# o_clone_rev_f.net
KiCad netlist of a schematic drawn in EAGLE
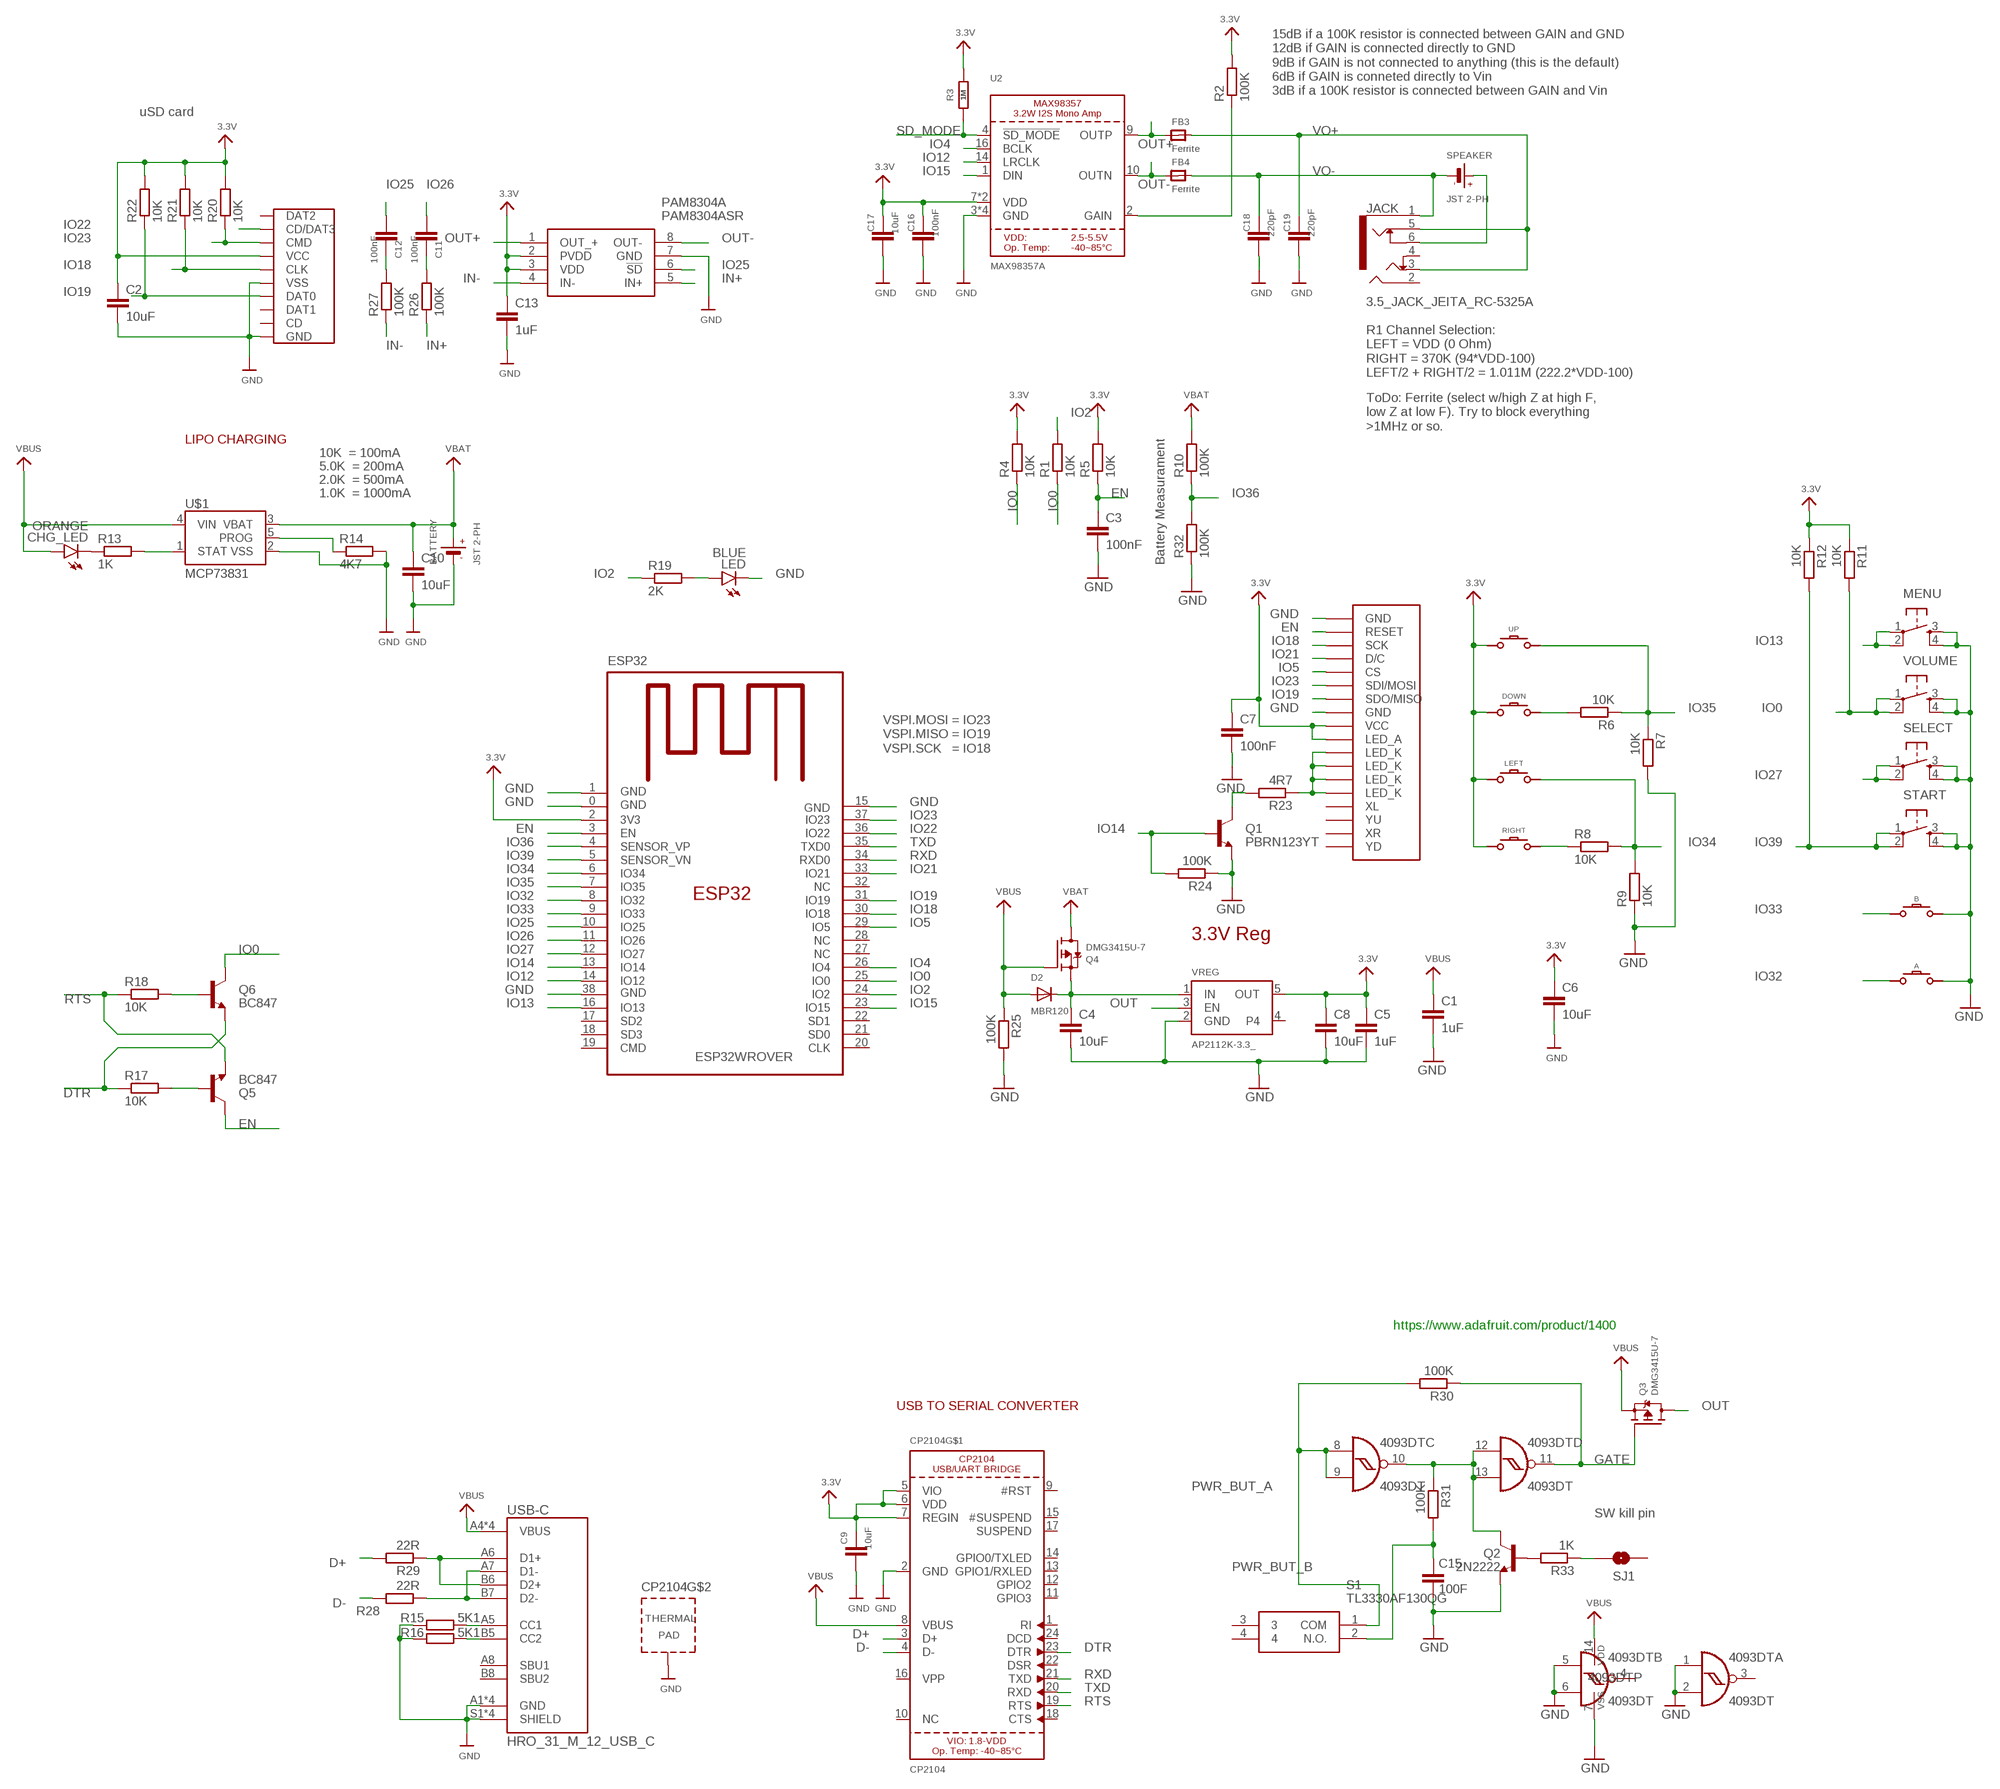
[diagram p0: schematic, sheet 1]

(export (version "E")
  (design (tool "Eeschema 10.0.6"))
  (components
    (comp (ref "4093DT")
      (value "4093DT")
      (footprint "eagle-import:MC14093B-TSSOP14")
      (libsource (lib "eagle-import") (part "4093DT"))
    )
    (comp (ref "A")
      (value "CONDUCTIVE_BUTTONCONDUCTIVE_BUTTON_THICK")
      (footprint "eagle-import:CONDUCTIVE_BUTTON_THICK")
      (libsource (lib "eagle-import") (part "CONDUCTIVE_BUTTONCONDUCTIVE_BUTTON_THICK"))
    )
    (comp (ref "B")
      (value "CONDUCTIVE_BUTTONCONDUCTIVE_BUTTON_THICK")
      (footprint "eagle-import:CONDUCTIVE_BUTTON_THICK")
      (libsource (lib "eagle-import") (part "CONDUCTIVE_BUTTONCONDUCTIVE_BUTTON_THICK"))
    )
    (comp (ref "BATTERY")
      (value "JST 2-PH")
      (footprint "eagle-import:JSTPH2")
      (libsource (lib "eagle-import") (part "JST_CONNECTOR"))
    )
    (comp (ref "C1")
      (value "1uF")
      (footprint "eagle-import:C0805")
      (libsource (lib "eagle-import") (part "C-EUC0805"))
    )
    (comp (ref "C2")
      (value "10uF")
      (footprint "eagle-import:C0805")
      (libsource (lib "eagle-import") (part "C-EUC0805"))
    )
    (comp (ref "C3")
      (value "100nF")
      (footprint "eagle-import:C0805")
      (libsource (lib "eagle-import") (part "C-EUC0805"))
    )
    (comp (ref "C4")
      (value "10uF")
      (footprint "eagle-import:C0805")
      (libsource (lib "eagle-import") (part "C-EUC0805"))
    )
    (comp (ref "C5")
      (value "1uF")
      (footprint "eagle-import:C0805")
      (libsource (lib "eagle-import") (part "C-EUC0805"))
    )
    (comp (ref "C6")
      (value "10uF")
      (footprint "eagle-import:C0805")
      (libsource (lib "eagle-import") (part "C-EUC0805"))
    )
    (comp (ref "C7")
      (value "100nF")
      (footprint "eagle-import:C0805")
      (libsource (lib "eagle-import") (part "C-EUC0805"))
    )
    (comp (ref "C8")
      (value "10uF")
      (footprint "eagle-import:C0805")
      (libsource (lib "eagle-import") (part "C-EUC0805"))
    )
    (comp (ref "C9")
      (value "10uF")
      (footprint "eagle-import:C0805")
      (libsource (lib "eagle-import") (part "C-EUC0805"))
    )
    (comp (ref "C10")
      (value "10uF")
      (footprint "eagle-import:C0805")
      (libsource (lib "eagle-import") (part "C-EUC0805"))
    )
    (comp (ref "C11")
      (value "100nF")
      (footprint "eagle-import:C0805")
      (libsource (lib "eagle-import") (part "C-EUC0805"))
    )
    (comp (ref "C12")
      (value "100nF")
      (footprint "eagle-import:C0805")
      (libsource (lib "eagle-import") (part "C-EUC0805"))
    )
    (comp (ref "C13")
      (value "1uF")
      (footprint "eagle-import:C0805")
      (libsource (lib "eagle-import") (part "C-EUC0805"))
    )
    (comp (ref "C15")
      (value "100F")
      (footprint "eagle-import:C0805")
      (libsource (lib "eagle-import") (part "C-EUC0805"))
    )
    (comp (ref "C16")
      (value "100nF")
      (footprint "eagle-import:C0805")
      (libsource (lib "eagle-import") (part "C-EUC0805"))
    )
    (comp (ref "C17")
      (value "10uF")
      (footprint "eagle-import:C0805")
      (libsource (lib "eagle-import") (part "C-EUC0805"))
    )
    (comp (ref "C18")
      (value "220pF")
      (footprint "eagle-import:C0805")
      (libsource (lib "eagle-import") (part "C-EUC0805"))
    )
    (comp (ref "C19")
      (value "220pF")
      (footprint "eagle-import:C0805")
      (libsource (lib "eagle-import") (part "C-EUC0805"))
    )
    (comp (ref "CHG_LED")
      (value "ORANGE")
      (footprint "eagle-import:CHIPLED_0805")
      (libsource (lib "eagle-import") (part "LEDCHIPLED_0805"))
    )
    (comp (ref "CP2104")
      (value "CP2104")
      (footprint "eagle-import:QFN24_4MM_SMSC")
      (libsource (lib "eagle-import") (part "CP2104"))
    )
    (comp (ref "D2")
      (value "MBR120")
      (footprint "eagle-import:SOD-123")
      (libsource (lib "eagle-import") (part "DIODESOD-123"))
    )
    (comp (ref "DOWN")
      (value "CONDUCTIVE_BUTTONCONDUCTIVE_BUTTON_DIRECTIONAL_THICK")
      (footprint "eagle-import:CONDUCTIVE_BUTTON_DIRECTIONAL_THICK")
      (libsource (lib "eagle-import") (part "CONDUCTIVE_BUTTONCONDUCTIVE_BUTTON_DIRECTIONAL_THICK"))
    )
    (comp (ref "ESP32")
      (value "ESP32WROVER")
      (footprint "eagle-import:ESP32WROVER")
      (libsource (lib "eagle-import") (part "ESP32WROVER"))
    )
    (comp (ref "FB3")
      (value "Ferrite")
      (footprint "eagle-import:0805")
      (libsource (lib "eagle-import") (part "FERRITE0805"))
    )
    (comp (ref "FB4")
      (value "Ferrite")
      (footprint "eagle-import:0805")
      (libsource (lib "eagle-import") (part "FERRITE0805"))
    )
    (comp (ref "JACK")
      (value "3.5_JACK_JEITA_RC-5325A")
      (footprint "eagle-import:3.5_JACK_JEITA_RC-5325A")
      (libsource (lib "eagle-import") (part "3.5_JACK_JEITA_RC-5325A"))
    )
    (comp (ref "LCD")
      (value "ILI9341_3.2LCD_")
      (footprint "eagle-import:LI9341_3.2LCD")
      (libsource (lib "eagle-import") (part "ILI9341_3.2LCD_"))
    )
    (comp (ref "LED")
      (value "BLUE")
      (footprint "eagle-import:CHIPLED_0805")
      (libsource (lib "eagle-import") (part "LEDCHIPLED_0805"))
    )
    (comp (ref "LEFT")
      (value "CONDUCTIVE_BUTTONCONDUCTIVE_BUTTON_DIRECTIONAL_THICK")
      (footprint "eagle-import:CONDUCTIVE_BUTTON_DIRECTIONAL_THICK")
      (libsource (lib "eagle-import") (part "CONDUCTIVE_BUTTONCONDUCTIVE_BUTTON_DIRECTIONAL_THICK"))
    )
    (comp (ref "MENU")
      (value "TACTILE_SWITCHE_5X5_MICRO\"")
      (footprint "eagle-import:TACTILE_SWITCH_5X5_MICRO")
      (libsource (lib "eagle-import") (part "TACTILE_SWITCHE_5X5_MICRO{dblquote}"))
    )
    (comp (ref "PAM8304A")
      (value "PAM8304ASR")
      (footprint "eagle-import:SOP65P490X110-8N")
      (fields (field (name "MOUSER_PART_NUMBER") "621-PAM8304ASR"))
      (libsource (lib "eagle-import") (part "PAM8304ASR"))
    )
    (comp (ref "Q1")
      (value "PBRN123YT")
      (footprint "eagle-import:SOT23-3")
      (libsource (lib "eagle-import") (part "TRANSISTOR_NPNSOT23-3"))
    )
    (comp (ref "Q2")
      (value "2N2222")
      (footprint "eagle-import:SOT23-BEC")
      (libsource (lib "eagle-import") (part "-NPN-SOT23-BECMMBT2222ALT1"))
    )
    (comp (ref "Q3")
      (value "DMG3415U-7")
      (footprint "eagle-import:SOT23-WIDE@1")
      (libsource (lib "eagle-import") (part "MOSFET-PWIDE"))
    )
    (comp (ref "Q4")
      (value "DMG3415U-7")
      (footprint "eagle-import:SOT23-R")
      (libsource (lib "eagle-import") (part "MOSFET-P"))
    )
    (comp (ref "Q5")
      (value "BC847")
      (footprint "eagle-import:SOT23-3")
      (libsource (lib "eagle-import") (part "TRANSISTOR_NPNSOT23-3"))
    )
    (comp (ref "Q6")
      (value "BC847")
      (footprint "eagle-import:SOT23-3")
      (libsource (lib "eagle-import") (part "TRANSISTOR_NPNSOT23-3"))
    )
    (comp (ref "R1")
      (value "10K")
      (footprint "eagle-import:R0805")
      (libsource (lib "eagle-import") (part "R-EU_R0805"))
    )
    (comp (ref "R2")
      (value "100K")
      (footprint "eagle-import:R0805")
      (libsource (lib "eagle-import") (part "R-EU_R0805"))
    )
    (comp (ref "R3")
      (value "1M")
      (footprint "eagle-import:R0805")
      (libsource (lib "eagle-import") (part "R-EU_R0805"))
    )
    (comp (ref "R4")
      (value "10K")
      (footprint "eagle-import:R0805")
      (libsource (lib "eagle-import") (part "R-EU_R0805"))
    )
    (comp (ref "R5")
      (value "10K")
      (footprint "eagle-import:R0805")
      (libsource (lib "eagle-import") (part "R-EU_R0805"))
    )
    (comp (ref "R6")
      (value "10K")
      (footprint "eagle-import:R0805")
      (libsource (lib "eagle-import") (part "R-EU_R0805"))
    )
    (comp (ref "R7")
      (value "10K")
      (footprint "eagle-import:R0805")
      (libsource (lib "eagle-import") (part "R-EU_R0805"))
    )
    (comp (ref "R8")
      (value "10K")
      (footprint "eagle-import:R0805")
      (libsource (lib "eagle-import") (part "R-EU_R0805"))
    )
    (comp (ref "R9")
      (value "10K")
      (footprint "eagle-import:R0805")
      (libsource (lib "eagle-import") (part "R-EU_R0805"))
    )
    (comp (ref "R10")
      (value "100K")
      (footprint "eagle-import:R0805")
      (libsource (lib "eagle-import") (part "R-EU_R0805"))
    )
    (comp (ref "R11")
      (value "10K")
      (footprint "eagle-import:R0805")
      (libsource (lib "eagle-import") (part "R-EU_R0805"))
    )
    (comp (ref "R12")
      (value "10K")
      (footprint "eagle-import:R0805")
      (libsource (lib "eagle-import") (part "R-EU_R0805"))
    )
    (comp (ref "R13")
      (value "1K")
      (footprint "eagle-import:R0805")
      (libsource (lib "eagle-import") (part "R-EU_R0805"))
    )
    (comp (ref "R14")
      (value "4K7")
      (footprint "eagle-import:R0805")
      (libsource (lib "eagle-import") (part "R-EU_R0805"))
    )
    (comp (ref "R15")
      (value "5K1")
      (footprint "eagle-import:R0805")
      (libsource (lib "eagle-import") (part "R-EU_R0805"))
    )
    (comp (ref "R16")
      (value "5K1")
      (footprint "eagle-import:R0805")
      (libsource (lib "eagle-import") (part "R-EU_R0805"))
    )
    (comp (ref "R17")
      (value "10K")
      (footprint "eagle-import:R0805")
      (libsource (lib "eagle-import") (part "R-EU_R0805"))
    )
    (comp (ref "R18")
      (value "10K")
      (footprint "eagle-import:R0805")
      (libsource (lib "eagle-import") (part "R-EU_R0805"))
    )
    (comp (ref "R19")
      (value "2K")
      (footprint "eagle-import:R0805")
      (libsource (lib "eagle-import") (part "R-EU_R0805"))
    )
    (comp (ref "R20")
      (value "10K")
      (footprint "eagle-import:R0805")
      (libsource (lib "eagle-import") (part "R-EU_R0805"))
    )
    (comp (ref "R21")
      (value "10K")
      (footprint "eagle-import:R0805")
      (libsource (lib "eagle-import") (part "R-EU_R0805"))
    )
    (comp (ref "R22")
      (value "10K")
      (footprint "eagle-import:R0805")
      (libsource (lib "eagle-import") (part "R-EU_R0805"))
    )
    (comp (ref "R23")
      (value "4R7")
      (footprint "eagle-import:R0805")
      (libsource (lib "eagle-import") (part "R-EU_R0805"))
    )
    (comp (ref "R24")
      (value "100K")
      (footprint "eagle-import:R0805")
      (libsource (lib "eagle-import") (part "R-EU_R0805"))
    )
    (comp (ref "R25")
      (value "100K")
      (footprint "eagle-import:R0805")
      (libsource (lib "eagle-import") (part "R-EU_R0805"))
    )
    (comp (ref "R26")
      (value "100K")
      (footprint "eagle-import:R0805")
      (libsource (lib "eagle-import") (part "R-EU_R0805"))
    )
    (comp (ref "R27")
      (value "100K")
      (footprint "eagle-import:R0805")
      (libsource (lib "eagle-import") (part "R-EU_R0805"))
    )
    (comp (ref "R28")
      (value "22R")
      (footprint "eagle-import:R0805")
      (libsource (lib "eagle-import") (part "R-EU_R0805"))
    )
    (comp (ref "R29")
      (value "22R")
      (footprint "eagle-import:R0805")
      (libsource (lib "eagle-import") (part "R-EU_R0805"))
    )
    (comp (ref "R30")
      (value "100K")
      (footprint "eagle-import:R0805")
      (libsource (lib "eagle-import") (part "R-EU_R0805"))
    )
    (comp (ref "R31")
      (value "100K")
      (footprint "eagle-import:R0805")
      (libsource (lib "eagle-import") (part "R-EU_R0805"))
    )
    (comp (ref "R32")
      (value "100K")
      (footprint "eagle-import:R0805")
      (libsource (lib "eagle-import") (part "R-EU_R0805"))
    )
    (comp (ref "R33")
      (value "1K")
      (footprint "eagle-import:R0805")
      (libsource (lib "eagle-import") (part "R-EU_R0805"))
    )
    (comp (ref "RIGHT")
      (value "CONDUCTIVE_BUTTONCONDUCTIVE_BUTTON_DIRECTIONAL_THICK")
      (footprint "eagle-import:CONDUCTIVE_BUTTON_DIRECTIONAL_THICK")
      (libsource (lib "eagle-import") (part "CONDUCTIVE_BUTTONCONDUCTIVE_BUTTON_DIRECTIONAL_THICK"))
    )
    (comp (ref "S1")
      (value "TL3330AF130QG")
      (footprint "eagle-import:TL3330AF130QG")
      (fields (field (name "MOUSER_PART_NUMBER") "612-TL3330AF130QG"))
      (libsource (lib "eagle-import") (part "TL3330AF130QG"))
    )
    (comp (ref "SD_CARD")
      (value "MICRO_SD_CARD\"")
      (footprint "eagle-import:TFP09-2--12B")
      (libsource (lib "eagle-import") (part "MICRO_SD_CARD{dblquote}"))
    )
    (comp (ref "SELECT")
      (value "TACTILE_SWITCHE_5X5_MICRO\"")
      (footprint "eagle-import:TACTILE_SWITCH_5X5_MICRO")
      (libsource (lib "eagle-import") (part "TACTILE_SWITCHE_5X5_MICRO{dblquote}"))
    )
    (comp (ref "SJ1")
      (value "SOLDERJUMPERNO")
      (footprint "eagle-import:SJ_2S-NO")
      (libsource (lib "eagle-import") (part "SOLDERJUMPERNO"))
    )
    (comp (ref "SPEAKER")
      (value "JST 2-PH")
      (footprint "eagle-import:JSTPH2")
      (libsource (lib "eagle-import") (part "JST_CONNECTOR"))
    )
    (comp (ref "START")
      (value "TACTILE_SWITCHE_5X5_MICRO\"")
      (footprint "eagle-import:TACTILE_SWITCH_5X5_MICRO")
      (libsource (lib "eagle-import") (part "TACTILE_SWITCHE_5X5_MICRO{dblquote}"))
    )
    (comp (ref "U$1")
      (value "MCP73831")
      (footprint "eagle-import:SOT95P290X120-5")
      (libsource (lib "eagle-import") (part "MCP73831"))
    )
    (comp (ref "U2")
      (value "MAX98357A")
      (footprint "eagle-import:QFN16_3MM")
      (libsource (lib "eagle-import") (part "AUDIOAMP_MAX98357"))
    )
    (comp (ref "UP")
      (value "CONDUCTIVE_BUTTONCONDUCTIVE_BUTTON_DIRECTIONAL_THICK")
      (footprint "eagle-import:CONDUCTIVE_BUTTON_DIRECTIONAL_THICK")
      (libsource (lib "eagle-import") (part "CONDUCTIVE_BUTTONCONDUCTIVE_BUTTON_DIRECTIONAL_THICK"))
    )
    (comp (ref "USB-C")
      (value "HRO_31_M_12_USB_C")
      (footprint "eagle-import:HRO_31_M_12_USB_C")
      (libsource (lib "eagle-import") (part "HRO_31_M_12_USB_C"))
    )
    (comp (ref "VOLUME")
      (value "TACTILE_SWITCHE_5X5_MICRO\"")
      (footprint "eagle-import:TACTILE_SWITCH_5X5_MICRO")
      (libsource (lib "eagle-import") (part "TACTILE_SWITCHE_5X5_MICRO{dblquote}"))
    )
    (comp (ref "VREG")
      (value "AP2112K-3.3_")
      (footprint "eagle-import:SOT95P290X120-5")
      (libsource (lib "eagle-import") (part "AP2112K-3.3_"))
    )
  )
  (nets
    (net (code "1") (name "/D+") (class "Default")
      (node (ref "CP2104") (pin "3") (pinfunction "D+_3") (pintype "bidirectional"))
      (node (ref "R29") (pin "2") (pinfunction "2_2") (pintype "passive"))
    )
    (net (code "2") (name "/D-") (class "Default")
      (node (ref "CP2104") (pin "4") (pinfunction "D-_4") (pintype "bidirectional"))
      (node (ref "R28") (pin "2") (pinfunction "2_2") (pintype "passive"))
    )
    (net (code "3") (name "/DTR") (class "Default")
      (node (ref "CP2104") (pin "23") (pinfunction "DTR_23") (pintype "output"))
      (node (ref "Q6") (pin "2") (pinfunction "E_2") (pintype "passive"))
      (node (ref "R17") (pin "1") (pinfunction "1_1") (pintype "passive"))
    )
    (net (code "4") (name "/EN") (class "Default")
      (node (ref "C3") (pin "1") (pinfunction "1_1") (pintype "passive"))
      (node (ref "ESP32") (pin "3") (pinfunction "EN_3") (pintype "bidirectional"))
      (node (ref "LCD") (pin "P$2") (pinfunction "RESET_P$2") (pintype "bidirectional"))
      (node (ref "Q5") (pin "3") (pinfunction "C_3") (pintype "passive"))
      (node (ref "R5") (pin "1") (pinfunction "1_1") (pintype "passive"))
    )
    (net (code "5") (name "/GATE") (class "Default")
      (node (ref "4093DT") (pin "11") (pinfunction "O_11") (pintype "output"))
      (node (ref "Q3") (pin "1") (pinfunction "G_1") (pintype "passive"))
      (node (ref "R30") (pin "1") (pinfunction "1_1") (pintype "passive"))
    )
    (net (code "6") (name "/IN+") (class "Default")
      (node (ref "PAM8304A") (pin "5") (pinfunction "IN+_5") (pintype "bidirectional"))
      (node (ref "R26") (pin "1") (pinfunction "1_1") (pintype "passive"))
    )
    (net (code "7") (name "/IN-") (class "Default")
      (node (ref "PAM8304A") (pin "4") (pinfunction "IN-_4") (pintype "bidirectional"))
      (node (ref "R27") (pin "1") (pinfunction "1_1") (pintype "passive"))
    )
    (net (code "8") (name "/IO0") (class "Default")
      (node (ref "ESP32") (pin "25") (pinfunction "IO0_25") (pintype "bidirectional"))
      (node (ref "Q6") (pin "3") (pinfunction "C_3") (pintype "passive"))
      (node (ref "R1") (pin "1") (pinfunction "1_1") (pintype "passive"))
      (node (ref "R11") (pin "2") (pinfunction "2_2") (pintype "passive"))
      (node (ref "R4") (pin "1") (pinfunction "1_1") (pintype "passive"))
      (node (ref "VOLUME") (pin "1") (pinfunction "1_1") (pintype "passive"))
      (node (ref "VOLUME") (pin "2") (pinfunction "2_2") (pintype "passive"))
    )
    (net (code "9") (name "/IO2") (class "Default")
      (node (ref "ESP32") (pin "24") (pinfunction "IO2_24") (pintype "bidirectional"))
      (node (ref "R1") (pin "2") (pinfunction "2_2") (pintype "passive"))
      (node (ref "R19") (pin "1") (pinfunction "1_1") (pintype "passive"))
    )
    (net (code "10") (name "/IO4") (class "Default")
      (node (ref "ESP32") (pin "26") (pinfunction "IO4_26") (pintype "bidirectional"))
      (node (ref "U2") (pin "16") (pinfunction "BCLK_16") (pintype "bidirectional"))
    )
    (net (code "11") (name "/IO5") (class "Default")
      (node (ref "ESP32") (pin "29") (pinfunction "IO5_29") (pintype "bidirectional"))
      (node (ref "LCD") (pin "P$5") (pinfunction "CS_P$5") (pintype "bidirectional"))
    )
    (net (code "12") (name "/IO12") (class "Default")
      (node (ref "ESP32") (pin "14") (pinfunction "IO12_14") (pintype "bidirectional"))
      (node (ref "U2") (pin "14") (pinfunction "LRCLK_14") (pintype "bidirectional"))
    )
    (net (code "13") (name "/IO13") (class "Default")
      (node (ref "ESP32") (pin "16") (pinfunction "IO13_16") (pintype "bidirectional"))
      (node (ref "MENU") (pin "1") (pinfunction "1_1") (pintype "passive"))
      (node (ref "MENU") (pin "2") (pinfunction "2_2") (pintype "passive"))
    )
    (net (code "14") (name "/IO14") (class "Default")
      (node (ref "ESP32") (pin "13") (pinfunction "IO14_13") (pintype "bidirectional"))
      (node (ref "Q1") (pin "1") (pinfunction "B_1") (pintype "passive"))
      (node (ref "R24") (pin "2") (pinfunction "2_2") (pintype "passive"))
    )
    (net (code "15") (name "/IO15") (class "Default")
      (node (ref "ESP32") (pin "23") (pinfunction "IO15_23") (pintype "bidirectional"))
      (node (ref "U2") (pin "1") (pinfunction "DIN_1") (pintype "bidirectional"))
    )
    (net (code "16") (name "/IO18") (class "Default")
      (node (ref "ESP32") (pin "30") (pinfunction "IO18_30") (pintype "bidirectional"))
      (node (ref "LCD") (pin "P$3") (pinfunction "SCK_P$3") (pintype "bidirectional"))
      (node (ref "R21") (pin "1") (pinfunction "1_1") (pintype "passive"))
      (node (ref "SD_CARD") (pin "CLK") (pinfunction "CLK_CLK") (pintype "bidirectional"))
    )
    (net (code "17") (name "/IO19") (class "Default")
      (node (ref "ESP32") (pin "31") (pinfunction "IO19_31") (pintype "bidirectional"))
      (node (ref "LCD") (pin "P$7") (pinfunction "SDO/MISO_P$7") (pintype "bidirectional"))
      (node (ref "R22") (pin "1") (pinfunction "1_1") (pintype "passive"))
      (node (ref "SD_CARD") (pin "DAT0") (pinfunction "DAT0_DAT0") (pintype "bidirectional"))
    )
    (net (code "18") (name "/IO21") (class "Default")
      (node (ref "ESP32") (pin "33") (pinfunction "IO21_33") (pintype "bidirectional"))
      (node (ref "LCD") (pin "P$4") (pinfunction "D/C_P$4") (pintype "bidirectional"))
    )
    (net (code "19") (name "/IO22") (class "Default")
      (node (ref "ESP32") (pin "36") (pinfunction "IO22_36") (pintype "bidirectional"))
      (node (ref "SD_CARD") (pin "CD/DAT3") (pinfunction "CD/DAT3_CD/DAT3") (pintype "bidirectional"))
    )
    (net (code "20") (name "/IO23") (class "Default")
      (node (ref "ESP32") (pin "37") (pinfunction "IO23_37") (pintype "bidirectional"))
      (node (ref "LCD") (pin "P$6") (pinfunction "SDI/MOSI_P$6") (pintype "bidirectional"))
      (node (ref "R20") (pin "1") (pinfunction "1_1") (pintype "passive"))
      (node (ref "SD_CARD") (pin "CMD") (pinfunction "CMD_CMD") (pintype "bidirectional"))
    )
    (net (code "21") (name "/IO25") (class "Default")
      (node (ref "C12") (pin "2") (pinfunction "2_2") (pintype "passive"))
      (node (ref "ESP32") (pin "10") (pinfunction "IO25_10") (pintype "bidirectional"))
      (node (ref "PAM8304A") (pin "6") (pinfunction "~{SD}_6") (pintype "bidirectional"))
    )
    (net (code "22") (name "/IO26") (class "Default")
      (node (ref "C11") (pin "2") (pinfunction "2_2") (pintype "passive"))
      (node (ref "ESP32") (pin "11") (pinfunction "IO26_11") (pintype "bidirectional"))
    )
    (net (code "23") (name "/IO27") (class "Default")
      (node (ref "ESP32") (pin "12") (pinfunction "IO27_12") (pintype "bidirectional"))
      (node (ref "SELECT") (pin "1") (pinfunction "1_1") (pintype "passive"))
      (node (ref "SELECT") (pin "2") (pinfunction "2_2") (pintype "passive"))
    )
    (net (code "24") (name "/IO32") (class "Default")
      (node (ref "A") (pin "P$GND") (pinfunction "P$GND_P$GND") (pintype "bidirectional"))
      (node (ref "ESP32") (pin "8") (pinfunction "IO32_8") (pintype "bidirectional"))
    )
    (net (code "25") (name "/IO33") (class "Default")
      (node (ref "B") (pin "P$GND") (pinfunction "P$GND_P$GND") (pintype "bidirectional"))
      (node (ref "ESP32") (pin "9") (pinfunction "IO33_9") (pintype "bidirectional"))
    )
    (net (code "26") (name "/IO34") (class "Default")
      (node (ref "ESP32") (pin "6") (pinfunction "IO34_6") (pintype "bidirectional"))
      (node (ref "LEFT") (pin "P$ACTIVE") (pinfunction "P$ACTIVE_P$ACTIVE") (pintype "bidirectional"))
      (node (ref "R8") (pin "2") (pinfunction "2_2") (pintype "passive"))
      (node (ref "R9") (pin "2") (pinfunction "2_2") (pintype "passive"))
    )
    (net (code "27") (name "/IO35") (class "Default")
      (node (ref "ESP32") (pin "7") (pinfunction "IO35_7") (pintype "bidirectional"))
      (node (ref "R6") (pin "1") (pinfunction "1_1") (pintype "passive"))
      (node (ref "R7") (pin "1") (pinfunction "1_1") (pintype "passive"))
      (node (ref "UP") (pin "P$ACTIVE") (pinfunction "P$ACTIVE_P$ACTIVE") (pintype "bidirectional"))
    )
    (net (code "28") (name "/IO36") (class "Default")
      (node (ref "ESP32") (pin "4") (pinfunction "SENSOR_VP_4") (pintype "bidirectional"))
      (node (ref "R10") (pin "1") (pinfunction "1_1") (pintype "passive"))
      (node (ref "R32") (pin "2") (pinfunction "2_2") (pintype "passive"))
    )
    (net (code "29") (name "/IO39") (class "Default")
      (node (ref "ESP32") (pin "5") (pinfunction "SENSOR_VN_5") (pintype "bidirectional"))
      (node (ref "R12") (pin "2") (pinfunction "2_2") (pintype "passive"))
      (node (ref "START") (pin "1") (pinfunction "1_1") (pintype "passive"))
      (node (ref "START") (pin "2") (pinfunction "2_2") (pintype "passive"))
    )
    (net (code "30") (name "/OUT") (class "Default")
      (node (ref "Q3") (pin "3") (pinfunction "D_3") (pintype "passive"))
      (node (ref "VREG") (pin "3") (pinfunction "EN_3") (pintype "bidirectional"))
    )
    (net (code "31") (name "/OUT+") (class "Default")
      (node (ref "FB3") (pin "1") (pinfunction "P$1_1") (pintype "passive"))
      (node (ref "PAM8304A") (pin "1") (pinfunction "OUT_+_1") (pintype "bidirectional"))
      (node (ref "U2") (pin "9") (pinfunction "OUTP_9") (pintype "output"))
    )
    (net (code "32") (name "/OUT-") (class "Default")
      (node (ref "FB4") (pin "1") (pinfunction "P$1_1") (pintype "passive"))
      (node (ref "PAM8304A") (pin "8") (pinfunction "OUT-_8") (pintype "bidirectional"))
      (node (ref "U2") (pin "10") (pinfunction "OUTN_10") (pintype "output"))
    )
    (net (code "33") (name "/PWR_BUT_A") (class "Default")
      (node (ref "4093DT") (pin "8") (pinfunction "I0_8") (pintype "input"))
      (node (ref "4093DT") (pin "9") (pinfunction "I1_9") (pintype "input"))
      (node (ref "R30") (pin "2") (pinfunction "2_2") (pintype "passive"))
      (node (ref "S1") (pin "1") (pinfunction "COM_1") (pintype "bidirectional"))
    )
    (net (code "34") (name "/PWR_BUT_B") (class "Default")
      (node (ref "C15") (pin "1") (pinfunction "1_1") (pintype "passive"))
      (node (ref "R31") (pin "2") (pinfunction "2_2") (pintype "passive"))
      (node (ref "S1") (pin "2") (pinfunction "N.O._2") (pintype "bidirectional"))
    )
    (net (code "35") (name "/RTS") (class "Default")
      (node (ref "CP2104") (pin "19") (pinfunction "RTS_19") (pintype "output"))
      (node (ref "Q5") (pin "2") (pinfunction "E_2") (pintype "passive"))
      (node (ref "R18") (pin "1") (pinfunction "1_1") (pintype "passive"))
    )
    (net (code "36") (name "/RXD") (class "Default")
      (node (ref "CP2104") (pin "21") (pinfunction "TXD_21") (pintype "output"))
      (node (ref "ESP32") (pin "34") (pinfunction "RXD0_34") (pintype "bidirectional"))
    )
    (net (code "37") (name "/SD_MODE") (class "Default")
      (node (ref "R3") (pin "1") (pinfunction "1_1") (pintype "passive"))
      (node (ref "U2") (pin "4") (pinfunction "~{SD_MODE}_4") (pintype "bidirectional"))
    )
    (net (code "38") (name "/TXD") (class "Default")
      (node (ref "CP2104") (pin "20") (pinfunction "RXD_20") (pintype "input"))
      (node (ref "ESP32") (pin "35") (pinfunction "TXD0_35") (pintype "bidirectional"))
    )
    (net (code "39") (name "/VO+") (class "Default")
      (node (ref "C19") (pin "1") (pinfunction "1_1") (pintype "passive"))
      (node (ref "FB3") (pin "2") (pinfunction "P$2_2") (pintype "passive"))
      (node (ref "JACK") (pin "3") (pinfunction "3_3") (pintype "bidirectional"))
      (node (ref "JACK") (pin "5") (pinfunction "5_5") (pintype "bidirectional"))
    )
    (net (code "40") (name "/VO-") (class "Default")
      (node (ref "C18") (pin "1") (pinfunction "1_1") (pintype "passive"))
      (node (ref "FB4") (pin "2") (pinfunction "P$2_2") (pintype "passive"))
      (node (ref "JACK") (pin "1") (pinfunction "1_1") (pintype "bidirectional"))
      (node (ref "SPEAKER") (pin "1") (pinfunction "-_1") (pintype "passive"))
    )
    (net (code "41") (name "3.3V") (class "Default")
      (node (ref "C13") (pin "1") (pinfunction "1_1") (pintype "passive"))
      (node (ref "C16") (pin "1") (pinfunction "1_1") (pintype "passive"))
      (node (ref "C17") (pin "1") (pinfunction "1_1") (pintype "passive"))
      (node (ref "C2") (pin "1") (pinfunction "1_1") (pintype "passive"))
      (node (ref "C5") (pin "1") (pinfunction "1_1") (pintype "passive"))
      (node (ref "C6") (pin "1") (pinfunction "1_1") (pintype "passive"))
      (node (ref "C7") (pin "1") (pinfunction "1_1") (pintype "passive"))
      (node (ref "C8") (pin "1") (pinfunction "1_1") (pintype "passive"))
      (node (ref "C9") (pin "1") (pinfunction "1_1") (pintype "passive"))
      (node (ref "CP2104") (pin "5") (pinfunction "VIO_5") (pintype "power_in"))
      (node (ref "CP2104") (pin "6") (pinfunction "VDD_6") (pintype "power_in"))
      (node (ref "CP2104") (pin "7") (pinfunction "REGIN_7") (pintype "power_in"))
      (node (ref "DOWN") (pin "P$GND") (pinfunction "P$GND_P$GND") (pintype "bidirectional"))
      (node (ref "ESP32") (pin "2") (pinfunction "3V3_2") (pintype "power_in"))
      (node (ref "LCD") (pin "P$10") (pinfunction "LED_A_P$10") (pintype "bidirectional"))
      (node (ref "LCD") (pin "P$9") (pinfunction "VCC_P$9") (pintype "bidirectional"))
      (node (ref "LEFT") (pin "P$GND") (pinfunction "P$GND_P$GND") (pintype "bidirectional"))
      (node (ref "PAM8304A") (pin "2") (pinfunction "PVDD_2") (pintype "bidirectional"))
      (node (ref "PAM8304A") (pin "3") (pinfunction "VDD_3") (pintype "bidirectional"))
      (node (ref "R11") (pin "1") (pinfunction "1_1") (pintype "passive"))
      (node (ref "R12") (pin "1") (pinfunction "1_1") (pintype "passive"))
      (node (ref "R2") (pin "2") (pinfunction "2_2") (pintype "passive"))
      (node (ref "R20") (pin "2") (pinfunction "2_2") (pintype "passive"))
      (node (ref "R21") (pin "2") (pinfunction "2_2") (pintype "passive"))
      (node (ref "R22") (pin "2") (pinfunction "2_2") (pintype "passive"))
      (node (ref "R3") (pin "2") (pinfunction "2_2") (pintype "passive"))
      (node (ref "R4") (pin "2") (pinfunction "2_2") (pintype "passive"))
      (node (ref "R5") (pin "2") (pinfunction "2_2") (pintype "passive"))
      (node (ref "RIGHT") (pin "P$GND") (pinfunction "P$GND_P$GND") (pintype "bidirectional"))
      (node (ref "SD_CARD") (pin "VCC") (pinfunction "VCC_VCC") (pintype "bidirectional"))
      (node (ref "U2") (pin "7") (pinfunction "VDD_7") (pintype "power_in"))
      (node (ref "U2") (pin "8") (pinfunction "VDD_8") (pintype "power_in"))
      (node (ref "UP") (pin "P$GND") (pinfunction "P$GND_P$GND") (pintype "bidirectional"))
      (node (ref "VREG") (pin "5") (pinfunction "OUT_5") (pintype "bidirectional"))
    )
    (net (code "42") (name "GND") (class "Default")
      (node (ref "4093DT") (pin "1") (pinfunction "I0_1") (pintype "input"))
      (node (ref "4093DT") (pin "2") (pinfunction "I1_2") (pintype "input"))
      (node (ref "4093DT") (pin "5") (pinfunction "I0_5") (pintype "input"))
      (node (ref "4093DT") (pin "6") (pinfunction "I1_6") (pintype "input"))
      (node (ref "4093DT") (pin "7") (pinfunction "VSS_7") (pintype "power_in"))
      (node (ref "A") (pin "P$ACTIVE") (pinfunction "P$ACTIVE_P$ACTIVE") (pintype "bidirectional"))
      (node (ref "B") (pin "P$ACTIVE") (pinfunction "P$ACTIVE_P$ACTIVE") (pintype "bidirectional"))
      (node (ref "BATTERY") (pin "1") (pinfunction "-_1") (pintype "passive"))
      (node (ref "C1") (pin "2") (pinfunction "2_2") (pintype "passive"))
      (node (ref "C10") (pin "2") (pinfunction "2_2") (pintype "passive"))
      (node (ref "C13") (pin "2") (pinfunction "2_2") (pintype "passive"))
      (node (ref "C15") (pin "2") (pinfunction "2_2") (pintype "passive"))
      (node (ref "C16") (pin "2") (pinfunction "2_2") (pintype "passive"))
      (node (ref "C17") (pin "2") (pinfunction "2_2") (pintype "passive"))
      (node (ref "C18") (pin "2") (pinfunction "2_2") (pintype "passive"))
      (node (ref "C19") (pin "2") (pinfunction "2_2") (pintype "passive"))
      (node (ref "C2") (pin "2") (pinfunction "2_2") (pintype "passive"))
      (node (ref "C3") (pin "2") (pinfunction "2_2") (pintype "passive"))
      (node (ref "C4") (pin "2") (pinfunction "2_2") (pintype "passive"))
      (node (ref "C5") (pin "2") (pinfunction "2_2") (pintype "passive"))
      (node (ref "C6") (pin "2") (pinfunction "2_2") (pintype "passive"))
      (node (ref "C7") (pin "2") (pinfunction "2_2") (pintype "passive"))
      (node (ref "C8") (pin "2") (pinfunction "2_2") (pintype "passive"))
      (node (ref "C9") (pin "2") (pinfunction "2_2") (pintype "passive"))
      (node (ref "CP2104") (pin "2") (pinfunction "GND_2") (pintype "power_in"))
      (node (ref "CP2104") (pin "THERM") (pinfunction "TP_THERM") (pintype "power_in"))
      (node (ref "ESP32") (pin "0") (pinfunction "GND_0") (pintype "power_in"))
      (node (ref "ESP32") (pin "1") (pinfunction "GND_1") (pintype "power_in"))
      (node (ref "ESP32") (pin "15") (pinfunction "GND_15") (pintype "power_in"))
      (node (ref "ESP32") (pin "38") (pinfunction "GND_38") (pintype "power_in"))
      (node (ref "LCD") (pin "P$1") (pinfunction "GND_P$1") (pintype "bidirectional"))
      (node (ref "LCD") (pin "P$8") (pinfunction "GND_P$8") (pintype "bidirectional"))
      (node (ref "LED") (pin "C") (pinfunction "C_C") (pintype "passive"))
      (node (ref "MENU") (pin "3") (pinfunction "3_3") (pintype "passive"))
      (node (ref "MENU") (pin "4") (pinfunction "4_4") (pintype "passive"))
      (node (ref "PAM8304A") (pin "7") (pinfunction "GND_7") (pintype "bidirectional"))
      (node (ref "Q1") (pin "2") (pinfunction "E_2") (pintype "passive"))
      (node (ref "Q2") (pin "E") (pinfunction "E_E") (pintype "passive"))
      (node (ref "R14") (pin "2") (pinfunction "2_2") (pintype "passive"))
      (node (ref "R15") (pin "2") (pinfunction "2_2") (pintype "passive"))
      (node (ref "R16") (pin "2") (pinfunction "2_2") (pintype "passive"))
      (node (ref "R24") (pin "1") (pinfunction "1_1") (pintype "passive"))
      (node (ref "R25") (pin "2") (pinfunction "2_2") (pintype "passive"))
      (node (ref "R32") (pin "1") (pinfunction "1_1") (pintype "passive"))
      (node (ref "R7") (pin "2") (pinfunction "2_2") (pintype "passive"))
      (node (ref "R9") (pin "1") (pinfunction "1_1") (pintype "passive"))
      (node (ref "SD_CARD") (pin "GND") (pinfunction "GND_GND") (pintype "bidirectional"))
      (node (ref "SD_CARD") (pin "GND@1") (pinfunction "GND_GND@1") (pintype "bidirectional"))
      (node (ref "SD_CARD") (pin "GND@2") (pinfunction "GND_GND@2") (pintype "bidirectional"))
      (node (ref "SD_CARD") (pin "GND@3") (pinfunction "VSS_GND@3") (pintype "bidirectional"))
      (node (ref "SD_CARD") (pin "VSS") (pinfunction "GND_VSS") (pintype "bidirectional"))
      (node (ref "SELECT") (pin "3") (pinfunction "3_3") (pintype "passive"))
      (node (ref "SELECT") (pin "4") (pinfunction "4_4") (pintype "passive"))
      (node (ref "START") (pin "3") (pinfunction "3_3") (pintype "passive"))
      (node (ref "START") (pin "4") (pinfunction "4_4") (pintype "passive"))
      (node (ref "U$1") (pin "2") (pinfunction "VSS_2") (pintype "power_in"))
      (node (ref "U2") (pin "11") (pinfunction "GND_11") (pintype "power_in"))
      (node (ref "U2") (pin "15") (pinfunction "GND_15") (pintype "power_in"))
      (node (ref "U2") (pin "3") (pinfunction "GND_3") (pintype "power_in"))
      (node (ref "U2") (pin "THERMAL") (pinfunction "GND_THERMAL") (pintype "power_in"))
      (node (ref "USB-C") (pin "A1") (pinfunction "GND_A1") (pintype "passive"))
      (node (ref "USB-C") (pin "A12") (pinfunction "GND_A12") (pintype "passive"))
      (node (ref "USB-C") (pin "B1") (pinfunction "GND_B1") (pintype "passive"))
      (node (ref "USB-C") (pin "B12") (pinfunction "GND_B12") (pintype "passive"))
      (node (ref "USB-C") (pin "S1") (pinfunction "SHIELD_S1") (pintype "passive"))
      (node (ref "USB-C") (pin "S2") (pinfunction "SHIELD_S2") (pintype "passive"))
      (node (ref "USB-C") (pin "S3") (pinfunction "SHIELD_S3") (pintype "passive"))
      (node (ref "USB-C") (pin "S4") (pinfunction "SHIELD_S4") (pintype "passive"))
      (node (ref "VOLUME") (pin "3") (pinfunction "3_3") (pintype "passive"))
      (node (ref "VOLUME") (pin "4") (pinfunction "4_4") (pintype "passive"))
      (node (ref "VREG") (pin "2") (pinfunction "GND_2") (pintype "bidirectional"))
    )
    (net (code "43") (name "Net-(4093DTC-O)") (class "Default")
      (node (ref "4093DT") (pin "10") (pinfunction "O_10") (pintype "output"))
      (node (ref "4093DT") (pin "12") (pinfunction "I0_12") (pintype "input"))
      (node (ref "4093DT") (pin "13") (pinfunction "I1_13") (pintype "input"))
      (node (ref "Q2") (pin "C") (pinfunction "C_C") (pintype "passive"))
      (node (ref "R31") (pin "1") (pinfunction "1_1") (pintype "passive"))
    )
    (net (code "44") (name "Net-(C11-Pad1)") (class "Default")
      (node (ref "C11") (pin "1") (pinfunction "1_1") (pintype "passive"))
      (node (ref "R26") (pin "2") (pinfunction "2_2") (pintype "passive"))
    )
    (net (code "45") (name "Net-(C12-Pad1)") (class "Default")
      (node (ref "C12") (pin "1") (pinfunction "1_1") (pintype "passive"))
      (node (ref "R27") (pin "2") (pinfunction "2_2") (pintype "passive"))
    )
    (net (code "46") (name "Net-(CHG_LED-PadC)") (class "Default")
      (node (ref "CHG_LED") (pin "C") (pinfunction "C_C") (pintype "passive"))
      (node (ref "R13") (pin "1") (pinfunction "1_1") (pintype "passive"))
    )
    (net (code "47") (name "Net-(DOWN-PadP$ACTIVE)") (class "Default")
      (node (ref "DOWN") (pin "P$ACTIVE") (pinfunction "P$ACTIVE_P$ACTIVE") (pintype "bidirectional"))
      (node (ref "R6") (pin "2") (pinfunction "2_2") (pintype "passive"))
    )
    (net (code "48") (name "Net-(LCD-LED_K-PadP$11)") (class "Default")
      (node (ref "LCD") (pin "P$11") (pinfunction "LED_K_P$11") (pintype "bidirectional"))
      (node (ref "LCD") (pin "P$12") (pinfunction "LED_K_P$12") (pintype "bidirectional"))
      (node (ref "LCD") (pin "P$13") (pinfunction "LED_K_P$13") (pintype "bidirectional"))
      (node (ref "LCD") (pin "P$14") (pinfunction "LED_K_P$14") (pintype "bidirectional"))
      (node (ref "R23") (pin "1") (pinfunction "1_1") (pintype "passive"))
    )
    (net (code "49") (name "Net-(LED-PadA)") (class "Default")
      (node (ref "LED") (pin "A") (pinfunction "A_A") (pintype "passive"))
      (node (ref "R19") (pin "2") (pinfunction "2_2") (pintype "passive"))
    )
    (net (code "50") (name "Net-(Q1-C)") (class "Default")
      (node (ref "Q1") (pin "3") (pinfunction "C_3") (pintype "passive"))
      (node (ref "R23") (pin "2") (pinfunction "2_2") (pintype "passive"))
    )
    (net (code "51") (name "Net-(Q2-PadB)") (class "Default")
      (node (ref "Q2") (pin "B") (pinfunction "B_B") (pintype "passive"))
      (node (ref "R33") (pin "2") (pinfunction "2_2") (pintype "passive"))
    )
    (net (code "52") (name "Net-(Q4-S)") (class "Default")
      (node (ref "C4") (pin "1") (pinfunction "1_1") (pintype "passive"))
      (node (ref "D2") (pin "C") (pinfunction "C_C") (pintype "passive"))
      (node (ref "Q4") (pin "2") (pinfunction "S_2") (pintype "passive"))
      (node (ref "VREG") (pin "1") (pinfunction "IN_1") (pintype "bidirectional"))
    )
    (net (code "53") (name "Net-(Q5-B)") (class "Default")
      (node (ref "Q5") (pin "1") (pinfunction "B_1") (pintype "passive"))
      (node (ref "R17") (pin "2") (pinfunction "2_2") (pintype "passive"))
    )
    (net (code "54") (name "Net-(Q6-B)") (class "Default")
      (node (ref "Q6") (pin "1") (pinfunction "B_1") (pintype "passive"))
      (node (ref "R18") (pin "2") (pinfunction "2_2") (pintype "passive"))
    )
    (net (code "55") (name "Net-(R8-Pad1)") (class "Default")
      (node (ref "R8") (pin "1") (pinfunction "1_1") (pintype "passive"))
      (node (ref "RIGHT") (pin "P$ACTIVE") (pinfunction "P$ACTIVE_P$ACTIVE") (pintype "bidirectional"))
    )
    (net (code "56") (name "Net-(R33-Pad1)") (class "Default")
      (node (ref "R33") (pin "1") (pinfunction "1_1") (pintype "passive"))
      (node (ref "SJ1") (pin "2") (pinfunction "2_2") (pintype "passive"))
    )
    (net (code "57") (name "Net-(SPEAKER-+)") (class "Default")
      (node (ref "JACK") (pin "6") (pinfunction "6_6") (pintype "bidirectional"))
      (node (ref "SPEAKER") (pin "2") (pinfunction "+_2") (pintype "passive"))
    )
    (net (code "58") (name "Net-(U$1-PROG)") (class "Default")
      (node (ref "R14") (pin "1") (pinfunction "1_1") (pintype "passive"))
      (node (ref "U$1") (pin "5") (pinfunction "PROG_5") (pintype "input"))
    )
    (net (code "59") (name "Net-(U$1-STAT)") (class "Default")
      (node (ref "R13") (pin "2") (pinfunction "2_2") (pintype "passive"))
      (node (ref "U$1") (pin "1") (pinfunction "STAT_1") (pintype "output"))
    )
    (net (code "60") (name "Net-(U2-GAIN)") (class "Default")
      (node (ref "R2") (pin "1") (pinfunction "1_1") (pintype "passive"))
      (node (ref "U2") (pin "2") (pinfunction "GAIN_2") (pintype "bidirectional"))
    )
    (net (code "61") (name "Net-(USB-C-CC1)") (class "Default")
      (node (ref "R15") (pin "1") (pinfunction "1_1") (pintype "passive"))
      (node (ref "USB-C") (pin "A5") (pinfunction "CC1_A5") (pintype "passive"))
    )
    (net (code "62") (name "Net-(USB-C-CC2)") (class "Default")
      (node (ref "R16") (pin "1") (pinfunction "1_1") (pintype "passive"))
      (node (ref "USB-C") (pin "B5") (pinfunction "CC2_B5") (pintype "passive"))
    )
    (net (code "63") (name "Net-(USB-C-D1+)") (class "Default")
      (node (ref "R29") (pin "1") (pinfunction "1_1") (pintype "passive"))
      (node (ref "USB-C") (pin "A6") (pinfunction "D1+_A6") (pintype "passive"))
      (node (ref "USB-C") (pin "B6") (pinfunction "D2+_B6") (pintype "passive"))
    )
    (net (code "64") (name "Net-(USB-C-D1-)") (class "Default")
      (node (ref "R28") (pin "1") (pinfunction "1_1") (pintype "passive"))
      (node (ref "USB-C") (pin "A7") (pinfunction "D1-_A7") (pintype "passive"))
      (node (ref "USB-C") (pin "B7") (pinfunction "D2-_B7") (pintype "passive"))
    )
    (net (code "65") (name "VBAT") (class "Default")
      (node (ref "BATTERY") (pin "2") (pinfunction "+_2") (pintype "passive"))
      (node (ref "C10") (pin "1") (pinfunction "1_1") (pintype "passive"))
      (node (ref "Q4") (pin "3") (pinfunction "D_3") (pintype "passive"))
      (node (ref "R10") (pin "2") (pinfunction "2_2") (pintype "passive"))
      (node (ref "U$1") (pin "3") (pinfunction "VBAT_3") (pintype "power_in"))
    )
    (net (code "66") (name "VBUS") (class "Default")
      (node (ref "4093DT") (pin "14") (pinfunction "VDD_14") (pintype "power_in"))
      (node (ref "C1") (pin "1") (pinfunction "1_1") (pintype "passive"))
      (node (ref "CHG_LED") (pin "A") (pinfunction "A_A") (pintype "passive"))
      (node (ref "CP2104") (pin "8") (pinfunction "VBUS_8") (pintype "power_in"))
      (node (ref "D2") (pin "A") (pinfunction "A_A") (pintype "passive"))
      (node (ref "Q3") (pin "2") (pinfunction "S_2") (pintype "passive"))
      (node (ref "Q4") (pin "1") (pinfunction "G_1") (pintype "passive"))
      (node (ref "R25") (pin "1") (pinfunction "1_1") (pintype "passive"))
      (node (ref "U$1") (pin "4") (pinfunction "VIN_4") (pintype "power_in"))
      (node (ref "USB-C") (pin "A4") (pinfunction "VBUS_A4") (pintype "passive"))
      (node (ref "USB-C") (pin "A9") (pinfunction "VBUS_A9") (pintype "passive"))
      (node (ref "USB-C") (pin "B4") (pinfunction "VBUS_B4") (pintype "passive"))
      (node (ref "USB-C") (pin "B9") (pinfunction "VBUS_B9") (pintype "passive"))
    )
    (net (code "67") (name "unconnected-(4093DTA-O-Pad3)") (class "Default")
      (node (ref "4093DT") (pin "3") (pinfunction "O_3") (pintype "output"))
    )
    (net (code "68") (name "unconnected-(4093DTB-O-Pad4)") (class "Default")
      (node (ref "4093DT") (pin "4") (pinfunction "O_4") (pintype "output"))
    )
    (net (code "69") (name "unconnected-(CP2104A-#RST-Pad9)") (class "Default")
      (node (ref "CP2104") (pin "9") (pinfunction "#RST_9") (pintype "bidirectional"))
    )
    (net (code "70") (name "unconnected-(CP2104A-#SUSPEND-Pad15)") (class "Default")
      (node (ref "CP2104") (pin "15") (pinfunction "#SUSPEND_15") (pintype "output"))
    )
    (net (code "71") (name "unconnected-(CP2104A-CTS-Pad18)") (class "Default")
      (node (ref "CP2104") (pin "18") (pinfunction "CTS_18") (pintype "input"))
    )
    (net (code "72") (name "unconnected-(CP2104A-DCD-Pad24)") (class "Default")
      (node (ref "CP2104") (pin "24") (pinfunction "DCD_24") (pintype "input"))
    )
    (net (code "73") (name "unconnected-(CP2104A-DSR-Pad22)") (class "Default")
      (node (ref "CP2104") (pin "22") (pinfunction "DSR_22") (pintype "input"))
    )
    (net (code "74") (name "unconnected-(CP2104A-GPIO0{slash}TXLED-Pad14)") (class "Default")
      (node (ref "CP2104") (pin "14") (pinfunction "GPIO0/TXLED_14") (pintype "bidirectional"))
    )
    (net (code "75") (name "unconnected-(CP2104A-GPIO1{slash}RXLED-Pad13)") (class "Default")
      (node (ref "CP2104") (pin "13") (pinfunction "GPIO1/RXLED_13") (pintype "bidirectional"))
    )
    (net (code "76") (name "unconnected-(CP2104A-GPIO2-Pad12)") (class "Default")
      (node (ref "CP2104") (pin "12") (pinfunction "GPIO2_12") (pintype "bidirectional"))
    )
    (net (code "77") (name "unconnected-(CP2104A-GPIO3-Pad11)") (class "Default")
      (node (ref "CP2104") (pin "11") (pinfunction "GPIO3_11") (pintype "bidirectional"))
    )
    (net (code "78") (name "unconnected-(CP2104A-NC-Pad10)") (class "Default")
      (node (ref "CP2104") (pin "10") (pinfunction "NC_10") (pintype "no_connect"))
    )
    (net (code "79") (name "unconnected-(CP2104A-RI-Pad1)") (class "Default")
      (node (ref "CP2104") (pin "1") (pinfunction "RI_1") (pintype "input"))
    )
    (net (code "80") (name "unconnected-(CP2104A-SUSPEND-Pad17)") (class "Default")
      (node (ref "CP2104") (pin "17") (pinfunction "SUSPEND_17") (pintype "output"))
    )
    (net (code "81") (name "unconnected-(CP2104A-VPP-Pad16)") (class "Default")
      (node (ref "CP2104") (pin "16") (pinfunction "VPP_16") (pintype "bidirectional"))
    )
    (net (code "82") (name "unconnected-(ESP32-CLK-Pad20)") (class "Default")
      (node (ref "ESP32") (pin "20") (pinfunction "CLK_20") (pintype "bidirectional"))
    )
    (net (code "83") (name "unconnected-(ESP32-CMD-Pad19)") (class "Default")
      (node (ref "ESP32") (pin "19") (pinfunction "CMD_19") (pintype "bidirectional"))
    )
    (net (code "84") (name "unconnected-(ESP32-NC-Pad27)") (class "Default")
      (node (ref "ESP32") (pin "27") (pinfunction "NC_27") (pintype "bidirectional"))
    )
    (net (code "85") (name "unconnected-(ESP32-NC-Pad28)") (class "Default")
      (node (ref "ESP32") (pin "28") (pinfunction "NC_28") (pintype "bidirectional"))
    )
    (net (code "86") (name "unconnected-(ESP32-NC-Pad32)") (class "Default")
      (node (ref "ESP32") (pin "32") (pinfunction "NC_32") (pintype "bidirectional"))
    )
    (net (code "87") (name "unconnected-(ESP32-SD0-Pad21)") (class "Default")
      (node (ref "ESP32") (pin "21") (pinfunction "SD0_21") (pintype "bidirectional"))
    )
    (net (code "88") (name "unconnected-(ESP32-SD1-Pad22)") (class "Default")
      (node (ref "ESP32") (pin "22") (pinfunction "SD1_22") (pintype "bidirectional"))
    )
    (net (code "89") (name "unconnected-(ESP32-SD2-Pad17)") (class "Default")
      (node (ref "ESP32") (pin "17") (pinfunction "SD2_17") (pintype "bidirectional"))
    )
    (net (code "90") (name "unconnected-(ESP32-SD3-Pad18)") (class "Default")
      (node (ref "ESP32") (pin "18") (pinfunction "SD3_18") (pintype "bidirectional"))
    )
    (net (code "91") (name "unconnected-(JACK-Pad2)") (class "Default")
      (node (ref "JACK") (pin "2") (pinfunction "2_2") (pintype "bidirectional"))
    )
    (net (code "92") (name "unconnected-(JACK-Pad4)") (class "Default")
      (node (ref "JACK") (pin "4") (pinfunction "4_4") (pintype "bidirectional"))
    )
    (net (code "93") (name "unconnected-(LCD-XL-PadP$15)") (class "Default")
      (node (ref "LCD") (pin "P$15") (pinfunction "XL_P$15") (pintype "bidirectional"))
    )
    (net (code "94") (name "unconnected-(LCD-XR-PadP$16)") (class "Default")
      (node (ref "LCD") (pin "P$16") (pinfunction "XR_P$16") (pintype "bidirectional"))
    )
    (net (code "95") (name "unconnected-(LCD-YD-PadP$17)") (class "Default")
      (node (ref "LCD") (pin "P$17") (pinfunction "YD_P$17") (pintype "bidirectional"))
    )
    (net (code "96") (name "unconnected-(LCD-YU-PadP$18)") (class "Default")
      (node (ref "LCD") (pin "P$18") (pinfunction "YU_P$18") (pintype "bidirectional"))
    )
    (net (code "97") (name "unconnected-(S1-Pad3)") (class "Default")
      (node (ref "S1") (pin "3") (pinfunction "3_3") (pintype "bidirectional"))
    )
    (net (code "98") (name "unconnected-(S1-Pad4)") (class "Default")
      (node (ref "S1") (pin "4") (pinfunction "4_4") (pintype "bidirectional"))
    )
    (net (code "99") (name "unconnected-(SD_CARD-PadCD)") (class "Default")
      (node (ref "SD_CARD") (pin "CD") (pinfunction "CD_CD") (pintype "bidirectional"))
    )
    (net (code "100") (name "unconnected-(SD_CARD-PadDAT1)") (class "Default")
      (node (ref "SD_CARD") (pin "DAT1") (pinfunction "DAT1_DAT1") (pintype "bidirectional"))
    )
    (net (code "101") (name "unconnected-(SD_CARD-PadDAT2)") (class "Default")
      (node (ref "SD_CARD") (pin "DAT2") (pinfunction "DAT2_DAT2") (pintype "bidirectional"))
    )
    (net (code "102") (name "unconnected-(SJ1-Pad1)") (class "Default")
      (node (ref "SJ1") (pin "1") (pinfunction "1_1") (pintype "passive"))
    )
    (net (code "103") (name "unconnected-(USB-C-SBU1-PadA8)") (class "Default")
      (node (ref "USB-C") (pin "A8") (pinfunction "SBU1_A8") (pintype "passive"))
    )
    (net (code "104") (name "unconnected-(USB-C-SBU2-PadB8)") (class "Default")
      (node (ref "USB-C") (pin "B8") (pinfunction "SBU2_B8") (pintype "passive"))
    )
    (net (code "105") (name "unconnected-(VREG-P4-Pad4)") (class "Default")
      (node (ref "VREG") (pin "4") (pinfunction "P4_4") (pintype "bidirectional"))
    )
  )
)
